# filtering-optical.net
KiCad netlist of a schematic drawn in Altium Designer
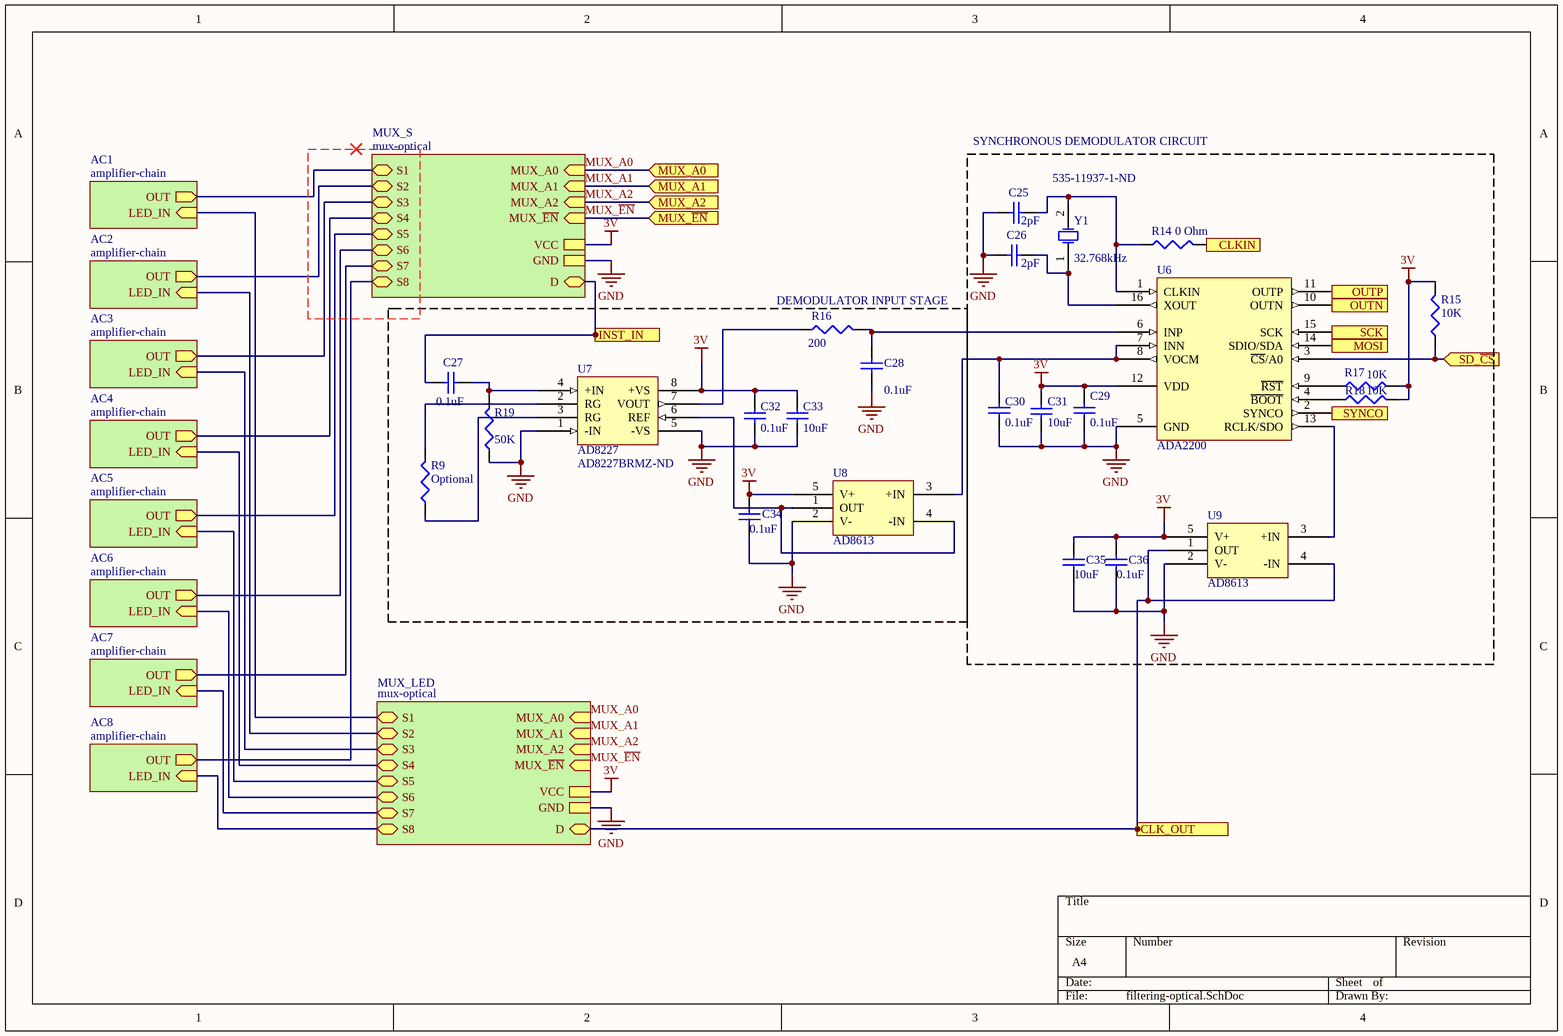
[diagram p0: filtering-optical.SchDoc]

(export (version "E")
  (design (tool "Eeschema 10.0.6"))
  (components
    (comp (ref "C25")
      (value "2pF")
      (footprint "0402")
      (description "Capacitor (Semiconductor SIM Model)")
      (fields (field (name "PUBLISHER") "Altium Limited"))
      (libsource (lib "Miscellaneous Devices") (part "Cap Semi"))
    )
    (comp (ref "C26")
      (value "2pF")
      (footprint "0402")
      (description "Capacitor (Semiconductor SIM Model)")
      (fields (field (name "PUBLISHER") "Altium Limited"))
      (libsource (lib "Miscellaneous Devices") (part "Cap Semi"))
    )
    (comp (ref "C27")
      (value "0.1uF")
      (footprint "0402")
      (description "Capacitor (Semiconductor SIM Model)")
      (fields (field (name "PUBLISHER") "Altium Limited"))
      (libsource (lib "Miscellaneous Devices") (part "Cap Semi"))
    )
    (comp (ref "C28")
      (value "0.1uF")
      (footprint "0402")
      (description "Capacitor (Semiconductor SIM Model)")
      (fields (field (name "PUBLISHER") "Altium Limited"))
      (libsource (lib "Miscellaneous Devices") (part "Cap Semi"))
    )
    (comp (ref "C29")
      (value "0.1uF")
      (footprint "0402")
      (description "Capacitor (Semiconductor SIM Model)")
      (fields (field (name "PUBLISHER") "Altium Limited"))
      (libsource (lib "Miscellaneous Devices") (part "Cap Semi"))
    )
    (comp (ref "C30")
      (value "0.1uF")
      (footprint "0402")
      (description "Capacitor (Semiconductor SIM Model)")
      (fields (field (name "PUBLISHER") "Altium Limited"))
      (libsource (lib "Miscellaneous Devices") (part "Cap Semi"))
    )
    (comp (ref "C31")
      (value "10uF")
      (footprint "1608[0603]")
      (description "Capacitor (Semiconductor SIM Model)")
      (fields (field (name "PUBLISHER") "Altium Limited"))
      (libsource (lib "Miscellaneous Devices") (part "Cap Semi"))
    )
    (comp (ref "C32")
      (value "0.1uF")
      (footprint "0402")
      (description "Capacitor (Semiconductor SIM Model)")
      (fields (field (name "PUBLISHER") "Altium Limited"))
      (libsource (lib "Miscellaneous Devices") (part "Cap Semi"))
    )
    (comp (ref "C33")
      (value "10uF")
      (footprint "1608[0603]")
      (description "Capacitor (Semiconductor SIM Model)")
      (fields (field (name "PUBLISHER") "Altium Limited"))
      (libsource (lib "Miscellaneous Devices") (part "Cap Semi"))
    )
    (comp (ref "C34")
      (value "0.1uF")
      (footprint "0402")
      (description "Capacitor (Semiconductor SIM Model)")
      (fields (field (name "PUBLISHER") "Altium Limited"))
      (libsource (lib "Miscellaneous Devices") (part "Cap Semi"))
    )
    (comp (ref "C35")
      (value "10uF")
      (footprint "1608[0603]")
      (description "Capacitor (Semiconductor SIM Model)")
      (fields (field (name "PUBLISHER") "Altium Limited"))
      (libsource (lib "Miscellaneous Devices") (part "Cap Semi"))
    )
    (comp (ref "C36")
      (value "0.1uF")
      (footprint "0402")
      (description "Capacitor (Semiconductor SIM Model)")
      (fields (field (name "PUBLISHER") "Altium Limited"))
      (libsource (lib "Miscellaneous Devices") (part "Cap Semi"))
    )
    (comp (ref "R9")
      (value "Optional")
      (footprint "0402")
      (description "Optional resistor to set gain on inst amp.")
      (fields (field (name "PUBLISHER") "Altium Limited"))
      (libsource (lib "Miscellaneous Devices") (part "Res3"))
    )
    (comp (ref "R14")
      (value "0 Ohm")
      (footprint "0402")
      (description "Resistor")
      (fields (field (name "PUBLISHER") "Altium Limited"))
      (libsource (lib "Miscellaneous Devices") (part "Res3"))
    )
    (comp (ref "R15")
      (value "10K")
      (footprint "0402")
      (description "Resistor")
      (fields (field (name "PUBLISHER") "Altium Limited"))
      (libsource (lib "Miscellaneous Devices") (part "Res3"))
    )
    (comp (ref "R16")
      (value "200")
      (footprint "0402")
      (description "Resistor")
      (fields (field (name "PUBLISHER") "Altium Limited"))
      (libsource (lib "Miscellaneous Devices") (part "Res3"))
    )
    (comp (ref "R17")
      (value "10K")
      (footprint "0402")
      (description "Resistor")
      (fields (field (name "PUBLISHER") "Altium Limited"))
      (libsource (lib "Miscellaneous Devices") (part "Res3"))
    )
    (comp (ref "R18")
      (value "10K")
      (footprint "0402")
      (description "Resistor")
      (fields (field (name "PUBLISHER") "Altium Limited"))
      (libsource (lib "Miscellaneous Devices") (part "Res3"))
    )
    (comp (ref "R19")
      (value "50K")
      (footprint "0402")
      (description "Resistor")
      (fields (field (name "PUBLISHER") "Altium Limited"))
      (libsource (lib "Miscellaneous Devices") (part "Res3"))
    )
    (comp (ref "U6")
      (value "ADA2200")
      (footprint "SSOP16_N")
      (description "Synchronous demodulator and configurable analog filter.")
      (libsource (lib "PAY") (part "ADA2200"))
    )
    (comp (ref "U7")
      (value "AD8227")
      (footprint "SOP8-65P300X300-8N")
      (description "Rail-to-rail instrumentation amplifier. Can operate on single supply.")
      (fields (field (name "SUPPLIER PART NUMBER 1") "AD8227BRMZ-ND"))
      (libsource (lib "PAY") (part "AD8227"))
    )
    (comp (ref "U8")
      (value "AD8613")
      (footprint "SOP-65P200X125-5N")
      (description "Low power, low noise rail-to-rail op-amp.")
      (libsource (lib "PAY") (part "AD8613"))
    )
    (comp (ref "U9")
      (value "AD8613")
      (footprint "SOP-65P200X125-5N")
      (description "Low power, low noise rail-to-rail op-amp.")
      (libsource (lib "PAY") (part "AD8613"))
    )
    (comp (ref "Y1")
      (value "32.768kHz")
      (footprint "ABS07-120-32.768")
      (description "Crystal Oscillator")
      (fields
        (field (name "SUPPLIER PART NUMBER") "535-11937-1-ND")
        (field (name "PUBLISHER") "Altium Limited")
      )
      (libsource (lib "Miscellaneous Devices") (part "XTAL"))
    )
  )
  (nets
    (net (code "1") (name "/CLKIN") (class "Default")
      (node (ref "R14") (pin "2") (pinfunction "2_2") (pintype "passive"))
    )
    (net (code "2") (name "/CLK_OUT") (class "Default")
      (node (ref "U9") (pin "1") (pinfunction "OUT_1") (pintype "passive"))
      (node (ref "U9") (pin "4") (pinfunction "-IN_4") (pintype "passive"))
    )
    (net (code "3") (name "/INST_IN") (class "Default")
      (node (ref "C27") (pin "2") (pinfunction "2_2") (pintype "passive"))
    )
    (net (code "12") (name "/MOSI") (class "Default")
      (node (ref "U6") (pin "14") (pinfunction "SDIO/SDA_14") (pintype "input"))
    )
    (net (code "18") (name "/OUTN") (class "Default")
      (node (ref "U6") (pin "10") (pinfunction "OUTN_10") (pintype "output"))
    )
    (net (code "19") (name "/OUTP") (class "Default")
      (node (ref "U6") (pin "11") (pinfunction "OUTP_11") (pintype "output"))
    )
    (net (code "27") (name "/SCK") (class "Default")
      (node (ref "U6") (pin "15") (pinfunction "SCK_15") (pintype "input"))
    )
    (net (code "28") (name "/SD_~{CS}") (class "Default")
      (node (ref "R15") (pin "1") (pinfunction "1_1") (pintype "passive"))
      (node (ref "U6") (pin "3") (pinfunction "~{CS}/A0_3") (pintype "input"))
    )
    (net (code "29") (name "/SYNCO") (class "Default")
      (node (ref "U6") (pin "2") (pinfunction "SYNCO_2") (pintype "output"))
    )
    (net (code "30") (name "3V") (class "Default")
      (node (ref "C29") (pin "2") (pinfunction "2_2") (pintype "passive"))
      (node (ref "C31") (pin "1") (pinfunction "1_1") (pintype "passive"))
      (node (ref "C32") (pin "2") (pinfunction "2_2") (pintype "passive"))
      (node (ref "C33") (pin "2") (pinfunction "2_2") (pintype "passive"))
      (node (ref "C34") (pin "2") (pinfunction "2_2") (pintype "passive"))
      (node (ref "C35") (pin "2") (pinfunction "2_2") (pintype "passive"))
      (node (ref "C36") (pin "2") (pinfunction "2_2") (pintype "passive"))
      (node (ref "R15") (pin "2") (pinfunction "2_2") (pintype "passive"))
      (node (ref "R17") (pin "2") (pinfunction "2_2") (pintype "passive"))
      (node (ref "R18") (pin "2") (pinfunction "2_2") (pintype "passive"))
      (node (ref "U6") (pin "12") (pinfunction "VDD_12") (pintype "power_in"))
      (node (ref "U7") (pin "8") (pinfunction "+VS_8") (pintype "power_in"))
      (node (ref "U8") (pin "5") (pinfunction "V+_5") (pintype "passive"))
      (node (ref "U9") (pin "5") (pinfunction "V+_5") (pintype "passive"))
    )
    (net (code "31") (name "GND") (class "Default")
      (node (ref "C25") (pin "2") (pinfunction "2_2") (pintype "passive"))
      (node (ref "C26") (pin "2") (pinfunction "2_2") (pintype "passive"))
      (node (ref "C28") (pin "1") (pinfunction "1_1") (pintype "passive"))
      (node (ref "C29") (pin "1") (pinfunction "1_1") (pintype "passive"))
      (node (ref "C30") (pin "1") (pinfunction "1_1") (pintype "passive"))
      (node (ref "C31") (pin "2") (pinfunction "2_2") (pintype "passive"))
      (node (ref "C32") (pin "1") (pinfunction "1_1") (pintype "passive"))
      (node (ref "C33") (pin "1") (pinfunction "1_1") (pintype "passive"))
      (node (ref "C34") (pin "1") (pinfunction "1_1") (pintype "passive"))
      (node (ref "C35") (pin "1") (pinfunction "1_1") (pintype "passive"))
      (node (ref "C36") (pin "1") (pinfunction "1_1") (pintype "passive"))
      (node (ref "R19") (pin "1") (pinfunction "1_1") (pintype "passive"))
      (node (ref "U6") (pin "5") (pinfunction "GND_5") (pintype "power_in"))
      (node (ref "U7") (pin "1") (pinfunction "-IN_1") (pintype "input"))
      (node (ref "U7") (pin "5") (pinfunction "-VS_5") (pintype "power_in"))
      (node (ref "U8") (pin "2") (pinfunction "V-_2") (pintype "passive"))
      (node (ref "U9") (pin "2") (pinfunction "V-_2") (pintype "passive"))
    )
    (net (code "32") (name "Net-(R9-Pad1)") (class "Default")
      (node (ref "R9") (pin "1") (pinfunction "1_1") (pintype "passive"))
      (node (ref "U7") (pin "3") (pinfunction "RG_3") (pintype "passive"))
    )
    (net (code "33") (name "Net-(R9-Pad2)") (class "Default")
      (node (ref "R9") (pin "2") (pinfunction "2_2") (pintype "passive"))
      (node (ref "U7") (pin "2") (pinfunction "RG_2") (pintype "passive"))
    )
    (net (code "34") (name "Net-(U6-CLKIN)") (class "Default")
      (node (ref "C25") (pin "1") (pinfunction "1_1") (pintype "passive"))
      (node (ref "R14") (pin "1") (pinfunction "1_1") (pintype "passive"))
      (node (ref "U6") (pin "1") (pinfunction "CLKIN_1") (pintype "input"))
      (node (ref "Y1") (pin "2") (pinfunction "OSC2_2") (pintype "passive"))
    )
    (net (code "35") (name "Net-(U6-INN)") (class "Default")
      (node (ref "C30") (pin "2") (pinfunction "2_2") (pintype "passive"))
      (node (ref "U6") (pin "7") (pinfunction "INN_7") (pintype "input"))
      (node (ref "U6") (pin "8") (pinfunction "VOCM_8") (pintype "output"))
      (node (ref "U8") (pin "3") (pinfunction "+IN_3") (pintype "passive"))
    )
    (net (code "36") (name "Net-(U6-INP)") (class "Default")
      (node (ref "C28") (pin "2") (pinfunction "2_2") (pintype "passive"))
      (node (ref "R16") (pin "2") (pinfunction "2_2") (pintype "passive"))
      (node (ref "U6") (pin "6") (pinfunction "INP_6") (pintype "input"))
    )
    (net (code "37") (name "Net-(U6-RCLK{slash}SDO)") (class "Default")
      (node (ref "U6") (pin "13") (pinfunction "RCLK/SDO_13") (pintype "output"))
      (node (ref "U9") (pin "3") (pinfunction "+IN_3") (pintype "passive"))
    )
    (net (code "38") (name "Net-(U6-XOUT)") (class "Default")
      (node (ref "C26") (pin "1") (pinfunction "1_1") (pintype "passive"))
      (node (ref "U6") (pin "16") (pinfunction "XOUT_16") (pintype "output"))
      (node (ref "Y1") (pin "1") (pinfunction "OSC1_1") (pintype "passive"))
    )
    (net (code "39") (name "Net-(U6-~{BOOT})") (class "Default")
      (node (ref "R18") (pin "1") (pinfunction "1_1") (pintype "passive"))
      (node (ref "U6") (pin "4") (pinfunction "~{BOOT}_4") (pintype "input"))
    )
    (net (code "40") (name "Net-(U6-~{RST})") (class "Default")
      (node (ref "R17") (pin "1") (pinfunction "1_1") (pintype "passive"))
      (node (ref "U6") (pin "9") (pinfunction "~{RST}_9") (pintype "input"))
    )
    (net (code "41") (name "Net-(U7-+IN)") (class "Default")
      (node (ref "C27") (pin "1") (pinfunction "1_1") (pintype "passive"))
      (node (ref "R19") (pin "2") (pinfunction "2_2") (pintype "passive"))
      (node (ref "U7") (pin "4") (pinfunction "+IN_4") (pintype "input"))
    )
    (net (code "42") (name "Net-(U7-REF)") (class "Default")
      (node (ref "U7") (pin "6") (pinfunction "REF_6") (pintype "input"))
      (node (ref "U8") (pin "1") (pinfunction "OUT_1") (pintype "passive"))
      (node (ref "U8") (pin "4") (pinfunction "-IN_4") (pintype "passive"))
    )
    (net (code "43") (name "Net-(U7-VOUT)") (class "Default")
      (node (ref "R16") (pin "1") (pinfunction "1_1") (pintype "passive"))
      (node (ref "U7") (pin "7") (pinfunction "VOUT_7") (pintype "output"))
    )
  )
)
